# DMGC-IPS-01_2-4.net
KiCad netlist of a schematic drawn in EAGLE
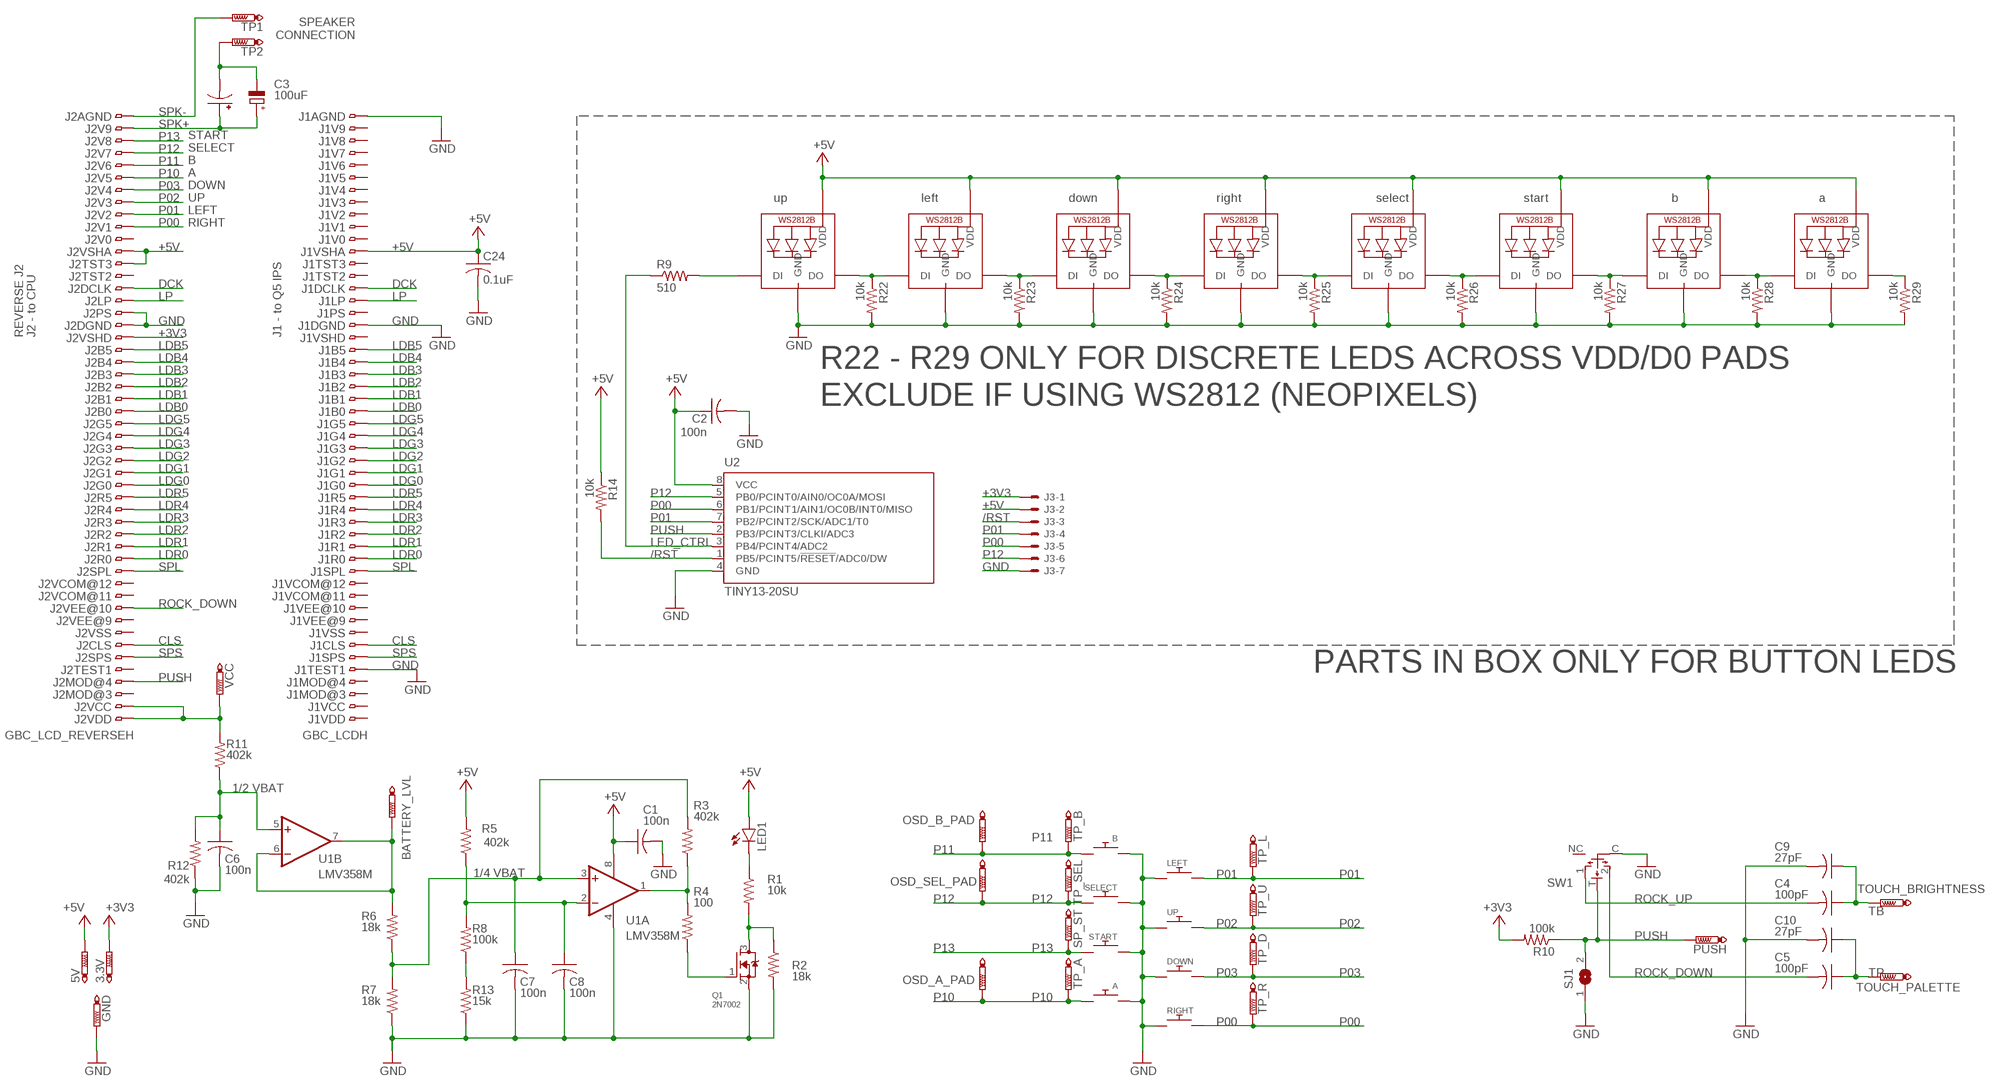
[diagram p0: schematic, sheet 1]

(export (version "E")
  (design (tool "Eeschema 10.0.6"))
  (components
    (comp (ref "3.3V")
      (value "PTR1TP20R")
      (footprint "eagle-import:TP20R")
      (libsource (lib "eagle-import") (part "PTR1TP20R"))
    )
    (comp (ref "5V")
      (value "PTR1TP20R")
      (footprint "eagle-import:TP20R")
      (libsource (lib "eagle-import") (part "PTR1TP20R"))
    )
    (comp (ref "A")
      (value "DMG-BTN")
      (footprint "eagle-import:DMG_BTN1")
      (libsource (lib "eagle-import") (part "DMG_BTN1"))
    )
    (comp (ref "B")
      (value "DMG-BTN")
      (footprint "eagle-import:DMG_BTN1")
      (libsource (lib "eagle-import") (part "DMG_BTN1"))
    )
    (comp (ref "BATTERY_LVL")
      (value "PTR1TP20R")
      (footprint "eagle-import:TP20R")
      (libsource (lib "eagle-import") (part "PTR1TP20R"))
    )
    (comp (ref "C1")
      (value "100n")
      (footprint "eagle-import:C0603")
      (libsource (lib "eagle-import") (part "C-USC0603"))
    )
    (comp (ref "C2")
      (value "100n")
      (footprint "eagle-import:C0603")
      (libsource (lib "eagle-import") (part "C-USC0603"))
    )
    (comp (ref "C3")
      (value "100uF")
      (footprint "eagle-import:CT3528")
      (libsource (lib "eagle-import") (part "CPOL-USCT3528"))
    )
    (comp (ref "C3TH")
      (value "CPOL-EUE2,5-6E")
      (footprint "eagle-import:E2,5-6E")
      (libsource (lib "eagle-import") (part "CPOL-EUE2,5-6E"))
    )
    (comp (ref "C4")
      (value "100pF")
      (footprint "eagle-import:C0603")
      (libsource (lib "eagle-import") (part "C-USC0603"))
    )
    (comp (ref "C5")
      (value "100pF")
      (footprint "eagle-import:C0603")
      (libsource (lib "eagle-import") (part "C-USC0603"))
    )
    (comp (ref "C6")
      (value "100n")
      (footprint "eagle-import:C0603")
      (libsource (lib "eagle-import") (part "C-USC0603"))
    )
    (comp (ref "C7")
      (value "100n")
      (footprint "eagle-import:C0603")
      (libsource (lib "eagle-import") (part "C-USC0603"))
    )
    (comp (ref "C8")
      (value "100n")
      (footprint "eagle-import:C0603")
      (libsource (lib "eagle-import") (part "C-USC0603"))
    )
    (comp (ref "C9")
      (value "27pF")
      (footprint "eagle-import:C0603")
      (libsource (lib "eagle-import") (part "C-USC0603"))
    )
    (comp (ref "C10")
      (value "27pF")
      (footprint "eagle-import:C0603")
      (libsource (lib "eagle-import") (part "C-USC0603"))
    )
    (comp (ref "C24")
      (value "0.1uF")
      (footprint "eagle-import:C0603")
      (libsource (lib "eagle-import") (part "C-USC0603"))
    )
    (comp (ref "DOWN")
      (value "DMG-BTN")
      (footprint "eagle-import:DMG_BTN1")
      (libsource (lib "eagle-import") (part "DMG_BTN1"))
    )
    (comp (ref "GND")
      (value "PTR1TP20R")
      (footprint "eagle-import:TP20R")
      (libsource (lib "eagle-import") (part "PTR1TP20R"))
    )
    (comp (ref "J1")
      (value "GBC_LCDH")
      (footprint "eagle-import:62684-502100AHLF")
      (fields (field (name "MPN") " 62684-502100AHLF"))
      (libsource (lib "eagle-import") (part "GBC_LCDH"))
    )
    (comp (ref "J2")
      (value "GBC_LCD_REVERSEH")
      (footprint "eagle-import:62684-502100AHLF_REVERSE")
      (libsource (lib "eagle-import") (part "GBC_LCD_REVERSEH"))
    )
    (comp (ref "J3")
      (value "C-GRID-07-15-91")
      (footprint "eagle-import:15-91-07")
      (fields (field (name "MF") "MOLEX"))
      (libsource (lib "eagle-import") (part "C-GRID-07-15-91"))
    )
    (comp (ref "LED1")
      (value "LED3MM")
      (footprint "eagle-import:LED3MM")
      (libsource (lib "eagle-import") (part "LED3MM"))
    )
    (comp (ref "LED10")
      (value "WS2812B3535")
      (footprint "eagle-import:LED3535")
      (libsource (lib "eagle-import") (part "WS2812B3535"))
    )
    (comp (ref "LED11")
      (value "WS2812B3535")
      (footprint "eagle-import:LED3535")
      (libsource (lib "eagle-import") (part "WS2812B3535"))
    )
    (comp (ref "LED12")
      (value "WS2812B3535")
      (footprint "eagle-import:LED3535")
      (libsource (lib "eagle-import") (part "WS2812B3535"))
    )
    (comp (ref "LED13")
      (value "WS2812B3535")
      (footprint "eagle-import:LED3535")
      (libsource (lib "eagle-import") (part "WS2812B3535"))
    )
    (comp (ref "LED14")
      (value "WS2812B3535")
      (footprint "eagle-import:LED3535")
      (libsource (lib "eagle-import") (part "WS2812B3535"))
    )
    (comp (ref "LED15")
      (value "WS2812B3535")
      (footprint "eagle-import:LED3535")
      (libsource (lib "eagle-import") (part "WS2812B3535"))
    )
    (comp (ref "LED16")
      (value "WS2812B3535")
      (footprint "eagle-import:LED3535")
      (libsource (lib "eagle-import") (part "WS2812B3535"))
    )
    (comp (ref "LED17")
      (value "WS2812B3535")
      (footprint "eagle-import:LED3535")
      (libsource (lib "eagle-import") (part "WS2812B3535"))
    )
    (comp (ref "LEFT")
      (value "DMG-BTN")
      (footprint "eagle-import:DMG_BTN1")
      (libsource (lib "eagle-import") (part "DMG_BTN1"))
    )
    (comp (ref "OSD_A_PAD")
      (value "PTR1TP20R")
      (footprint "eagle-import:TP20R")
      (libsource (lib "eagle-import") (part "PTR1TP20R"))
    )
    (comp (ref "OSD_B_PAD")
      (value "PTR1TP20R")
      (footprint "eagle-import:TP20R")
      (libsource (lib "eagle-import") (part "PTR1TP20R"))
    )
    (comp (ref "OSD_SEL_PAD")
      (value "PTR1TP20R")
      (footprint "eagle-import:TP20R")
      (libsource (lib "eagle-import") (part "PTR1TP20R"))
    )
    (comp (ref "PUSH")
      (value "PTR1TP20R")
      (footprint "eagle-import:TP20R")
      (libsource (lib "eagle-import") (part "PTR1TP20R"))
    )
    (comp (ref "Q1")
      (value "2N7002")
      (footprint "eagle-import:SOT23")
      (libsource (lib "eagle-import") (part "MOSFET-NREFLOW"))
    )
    (comp (ref "R1")
      (value "10k")
      (footprint "eagle-import:R0603")
      (libsource (lib "eagle-import") (part "R-US_R0603"))
    )
    (comp (ref "R2")
      (value "18k")
      (footprint "eagle-import:R0603")
      (libsource (lib "eagle-import") (part "R-US_R0603"))
    )
    (comp (ref "R3")
      (value "402k")
      (footprint "eagle-import:R0603")
      (libsource (lib "eagle-import") (part "R-US_R0603"))
    )
    (comp (ref "R4")
      (value "100")
      (footprint "eagle-import:R0603")
      (libsource (lib "eagle-import") (part "R-US_R0603"))
    )
    (comp (ref "R5")
      (value "402k")
      (footprint "eagle-import:R0603")
      (libsource (lib "eagle-import") (part "R-US_R0603"))
    )
    (comp (ref "R6")
      (value "18k")
      (footprint "eagle-import:R0603")
      (libsource (lib "eagle-import") (part "R-US_R0603"))
    )
    (comp (ref "R7")
      (value "18k")
      (footprint "eagle-import:R0603")
      (libsource (lib "eagle-import") (part "R-US_R0603"))
    )
    (comp (ref "R8")
      (value "100k")
      (footprint "eagle-import:R0603")
      (libsource (lib "eagle-import") (part "R-US_R0603"))
    )
    (comp (ref "R9")
      (value "510")
      (footprint "eagle-import:R0603")
      (libsource (lib "eagle-import") (part "R-US_R0603"))
    )
    (comp (ref "R10")
      (value "100k")
      (footprint "eagle-import:R0603")
      (libsource (lib "eagle-import") (part "R-US_R0603"))
    )
    (comp (ref "R11")
      (value "402k")
      (footprint "eagle-import:R0603")
      (libsource (lib "eagle-import") (part "R-US_R0603"))
    )
    (comp (ref "R12")
      (value "402k")
      (footprint "eagle-import:R0603")
      (libsource (lib "eagle-import") (part "R-US_R0603"))
    )
    (comp (ref "R13")
      (value "15k")
      (footprint "eagle-import:R0603")
      (libsource (lib "eagle-import") (part "R-US_R0603"))
    )
    (comp (ref "R14")
      (value "10k")
      (footprint "eagle-import:R0603")
      (libsource (lib "eagle-import") (part "R-US_R0603"))
    )
    (comp (ref "R22")
      (value "10k")
      (footprint "eagle-import:R0603")
      (libsource (lib "eagle-import") (part "R-US_R0603"))
    )
    (comp (ref "R23")
      (value "10k")
      (footprint "eagle-import:R0603")
      (libsource (lib "eagle-import") (part "R-US_R0603"))
    )
    (comp (ref "R24")
      (value "10k")
      (footprint "eagle-import:R0603")
      (libsource (lib "eagle-import") (part "R-US_R0603"))
    )
    (comp (ref "R25")
      (value "10k")
      (footprint "eagle-import:R0603")
      (libsource (lib "eagle-import") (part "R-US_R0603"))
    )
    (comp (ref "R26")
      (value "10k")
      (footprint "eagle-import:R0603")
      (libsource (lib "eagle-import") (part "R-US_R0603"))
    )
    (comp (ref "R27")
      (value "10k")
      (footprint "eagle-import:R0603")
      (libsource (lib "eagle-import") (part "R-US_R0603"))
    )
    (comp (ref "R28")
      (value "10k")
      (footprint "eagle-import:R0603")
      (libsource (lib "eagle-import") (part "R-US_R0603"))
    )
    (comp (ref "R29")
      (value "10k")
      (footprint "eagle-import:R0603")
      (libsource (lib "eagle-import") (part "R-US_R0603"))
    )
    (comp (ref "RIGHT")
      (value "DMG-BTN")
      (footprint "eagle-import:DMG_BTN1")
      (libsource (lib "eagle-import") (part "DMG_BTN1"))
    )
    (comp (ref "SELECT")
      (value "DMG-BTN")
      (footprint "eagle-import:DMG_BTN2_TACT2")
      (libsource (lib "eagle-import") (part "DMG_BTN2_TACT2"))
    )
    (comp (ref "SJ1") (value "SJ") (footprint "eagle-import:SJ") (libsource (lib "eagle-import") (part "SJ")))
    (comp (ref "SP_ST")
      (value "PTR1TP20R")
      (footprint "eagle-import:TP20R")
      (libsource (lib "eagle-import") (part "PTR1TP20R"))
    )
    (comp (ref "START")
      (value "DMG-BTN")
      (footprint "eagle-import:DMG_BTN2_TACT2")
      (libsource (lib "eagle-import") (part "DMG_BTN2_TACT2"))
    )
    (comp (ref "SW1")
      (value "NAV_SWITCH")
      (footprint "eagle-import:NAV_SWITCH")
      (libsource (lib "eagle-import") (part "NAV_SWITCH"))
    )
    (comp (ref "TOUCH_BRIGHTNESS")
      (value "PTR1TP20R")
      (footprint "eagle-import:TP20R")
      (libsource (lib "eagle-import") (part "PTR1TP20R"))
    )
    (comp (ref "TOUCH_PALETTE")
      (value "PTR1TP20R")
      (footprint "eagle-import:TP20R")
      (libsource (lib "eagle-import") (part "PTR1TP20R"))
    )
    (comp (ref "TP1")
      (value "PTR1PAD1-13")
      (footprint "eagle-import:P1-13")
      (libsource (lib "eagle-import") (part "testpad_385_PTR1PAD1-13"))
    )
    (comp (ref "TP2")
      (value "PTR1PAD1-13")
      (footprint "eagle-import:P1-13")
      (libsource (lib "eagle-import") (part "testpad_385_PTR1PAD1-13"))
    )
    (comp (ref "TP_A")
      (value "PTR1TP20R")
      (footprint "eagle-import:TP20R")
      (libsource (lib "eagle-import") (part "PTR1TP20R"))
    )
    (comp (ref "TP_B")
      (value "PTR1TP20R")
      (footprint "eagle-import:TP20R")
      (libsource (lib "eagle-import") (part "PTR1TP20R"))
    )
    (comp (ref "TP_D")
      (value "PTR1TP20R")
      (footprint "eagle-import:TP20R")
      (libsource (lib "eagle-import") (part "PTR1TP20R"))
    )
    (comp (ref "TP_L")
      (value "PTR1TP20R")
      (footprint "eagle-import:TP20R")
      (libsource (lib "eagle-import") (part "PTR1TP20R"))
    )
    (comp (ref "TP_R")
      (value "PTR1TP20R")
      (footprint "eagle-import:TP20R")
      (libsource (lib "eagle-import") (part "PTR1TP20R"))
    )
    (comp (ref "TP_SEL")
      (value "PTR1TP20R")
      (footprint "eagle-import:TP20R")
      (libsource (lib "eagle-import") (part "PTR1TP20R"))
    )
    (comp (ref "TP_U")
      (value "PTR1TP20R")
      (footprint "eagle-import:TP20R")
      (libsource (lib "eagle-import") (part "PTR1TP20R"))
    )
    (comp (ref "U1")
      (value "LMV358M")
      (footprint "eagle-import:SO08")
      (libsource (lib "eagle-import") (part "LMV358?M"))
    )
    (comp (ref "U2")
      (value "TINY13-20SU")
      (footprint "eagle-import:8S2")
      (fields (field (name "MPN") "ATTINY13-20SU"))
      (libsource (lib "eagle-import") (part "TINY13SU-20"))
    )
    (comp (ref "UP")
      (value "DMG-BTN")
      (footprint "eagle-import:DMG_BTN1")
      (libsource (lib "eagle-import") (part "DMG_BTN1"))
    )
    (comp (ref "VCC")
      (value "PTR1TP20R")
      (footprint "eagle-import:TP20R")
      (libsource (lib "eagle-import") (part "PTR1TP20R"))
    )
  )
  (nets
    (net (code "1") (name "+3V3") (class "Default")
      (node (ref "3.3V") (pin "TP") (pinfunction "TP_TP") (pintype "input"))
      (node (ref "J2") (pin "19") (pinfunction "1_19") (pintype "passive"))
      (node (ref "J3") (pin "1") (pinfunction "S_1") (pintype "passive"))
      (node (ref "R10") (pin "2") (pinfunction "2_2") (pintype "passive"))
    )
    (net (code "2") (name "+5V") (class "Default")
      (node (ref "5V") (pin "TP") (pinfunction "TP_TP") (pintype "input"))
      (node (ref "C1") (pin "1") (pinfunction "1_1") (pintype "passive"))
      (node (ref "C2") (pin "1") (pinfunction "1_1") (pintype "passive"))
      (node (ref "C24") (pin "1") (pinfunction "1_1") (pintype "passive"))
      (node (ref "J1") (pin "39") (pinfunction "1_39") (pintype "passive"))
      (node (ref "J2") (pin "12") (pinfunction "1_12") (pintype "passive"))
      (node (ref "J2") (pin "13") (pinfunction "1_13") (pintype "passive"))
      (node (ref "J3") (pin "2") (pinfunction "S_2") (pintype "passive"))
      (node (ref "LED1") (pin "A") (pinfunction "A_A") (pintype "passive"))
      (node (ref "LED10") (pin "4") (pinfunction "VDD_4") (pintype "power_in"))
      (node (ref "LED11") (pin "4") (pinfunction "VDD_4") (pintype "power_in"))
      (node (ref "LED12") (pin "4") (pinfunction "VDD_4") (pintype "power_in"))
      (node (ref "LED13") (pin "4") (pinfunction "VDD_4") (pintype "power_in"))
      (node (ref "LED14") (pin "4") (pinfunction "VDD_4") (pintype "power_in"))
      (node (ref "LED15") (pin "4") (pinfunction "VDD_4") (pintype "power_in"))
      (node (ref "LED16") (pin "4") (pinfunction "VDD_4") (pintype "power_in"))
      (node (ref "LED17") (pin "4") (pinfunction "VDD_4") (pintype "power_in"))
      (node (ref "R14") (pin "1") (pinfunction "1_1") (pintype "passive"))
      (node (ref "R5") (pin "2") (pinfunction "2_2") (pintype "passive"))
      (node (ref "U1") (pin "8") (pinfunction "V+_8") (pintype "power_in"))
      (node (ref "U2") (pin "8") (pinfunction "VCC_8") (pintype "power_in"))
    )
    (net (code "3") (name "/CLS") (class "Default")
      (node (ref "J1") (pin "7") (pinfunction "1_7") (pintype "passive"))
      (node (ref "J2") (pin "44") (pinfunction "1_44") (pintype "passive"))
    )
    (net (code "4") (name "/DCK") (class "Default")
      (node (ref "J1") (pin "36") (pinfunction "1_36") (pintype "passive"))
      (node (ref "J2") (pin "15") (pinfunction "1_15") (pintype "passive"))
    )
    (net (code "5") (name "/LDB0") (class "Default")
      (node (ref "J1") (pin "26") (pinfunction "1_26") (pintype "passive"))
      (node (ref "J2") (pin "25") (pinfunction "1_25") (pintype "passive"))
    )
    (net (code "6") (name "/LDB1") (class "Default")
      (node (ref "J1") (pin "27") (pinfunction "1_27") (pintype "passive"))
      (node (ref "J2") (pin "24") (pinfunction "1_24") (pintype "passive"))
    )
    (net (code "7") (name "/LDB2") (class "Default")
      (node (ref "J1") (pin "28") (pinfunction "1_28") (pintype "passive"))
      (node (ref "J2") (pin "23") (pinfunction "1_23") (pintype "passive"))
    )
    (net (code "8") (name "/LDB3") (class "Default")
      (node (ref "J1") (pin "29") (pinfunction "1_29") (pintype "passive"))
      (node (ref "J2") (pin "22") (pinfunction "1_22") (pintype "passive"))
    )
    (net (code "9") (name "/LDB4") (class "Default")
      (node (ref "J1") (pin "30") (pinfunction "1_30") (pintype "passive"))
      (node (ref "J2") (pin "21") (pinfunction "1_21") (pintype "passive"))
    )
    (net (code "10") (name "/LDB5") (class "Default")
      (node (ref "J1") (pin "31") (pinfunction "1_31") (pintype "passive"))
      (node (ref "J2") (pin "20") (pinfunction "1_20") (pintype "passive"))
    )
    (net (code "11") (name "/LDG0") (class "Default")
      (node (ref "J1") (pin "20") (pinfunction "1_20") (pintype "passive"))
      (node (ref "J2") (pin "31") (pinfunction "1_31") (pintype "passive"))
    )
    (net (code "12") (name "/LDG1") (class "Default")
      (node (ref "J1") (pin "21") (pinfunction "1_21") (pintype "passive"))
      (node (ref "J2") (pin "30") (pinfunction "1_30") (pintype "passive"))
    )
    (net (code "13") (name "/LDG2") (class "Default")
      (node (ref "J1") (pin "22") (pinfunction "1_22") (pintype "passive"))
      (node (ref "J2") (pin "29") (pinfunction "1_29") (pintype "passive"))
    )
    (net (code "14") (name "/LDG3") (class "Default")
      (node (ref "J1") (pin "23") (pinfunction "1_23") (pintype "passive"))
      (node (ref "J2") (pin "28") (pinfunction "1_28") (pintype "passive"))
    )
    (net (code "15") (name "/LDG4") (class "Default")
      (node (ref "J1") (pin "24") (pinfunction "1_24") (pintype "passive"))
      (node (ref "J2") (pin "27") (pinfunction "1_27") (pintype "passive"))
    )
    (net (code "16") (name "/LDG5") (class "Default")
      (node (ref "J1") (pin "25") (pinfunction "1_25") (pintype "passive"))
      (node (ref "J2") (pin "26") (pinfunction "1_26") (pintype "passive"))
    )
    (net (code "17") (name "/LDR0") (class "Default")
      (node (ref "J1") (pin "14") (pinfunction "1_14") (pintype "passive"))
      (node (ref "J2") (pin "37") (pinfunction "1_37") (pintype "passive"))
    )
    (net (code "18") (name "/LDR1") (class "Default")
      (node (ref "J1") (pin "15") (pinfunction "1_15") (pintype "passive"))
      (node (ref "J2") (pin "36") (pinfunction "1_36") (pintype "passive"))
    )
    (net (code "19") (name "/LDR2") (class "Default")
      (node (ref "J1") (pin "16") (pinfunction "1_16") (pintype "passive"))
      (node (ref "J2") (pin "35") (pinfunction "1_35") (pintype "passive"))
    )
    (net (code "20") (name "/LDR3") (class "Default")
      (node (ref "J1") (pin "17") (pinfunction "1_17") (pintype "passive"))
      (node (ref "J2") (pin "34") (pinfunction "1_34") (pintype "passive"))
    )
    (net (code "21") (name "/LDR4") (class "Default")
      (node (ref "J1") (pin "18") (pinfunction "1_18") (pintype "passive"))
      (node (ref "J2") (pin "33") (pinfunction "1_33") (pintype "passive"))
    )
    (net (code "22") (name "/LDR5") (class "Default")
      (node (ref "J1") (pin "19") (pinfunction "1_19") (pintype "passive"))
      (node (ref "J2") (pin "32") (pinfunction "1_32") (pintype "passive"))
    )
    (net (code "23") (name "/LED_CTRL") (class "Default")
      (node (ref "R9") (pin "1") (pinfunction "1_1") (pintype "passive"))
      (node (ref "U2") (pin "3") (pinfunction "PB4/PCINT4/ADC2_3") (pintype "bidirectional"))
    )
    (net (code "24") (name "/LP") (class "Default")
      (node (ref "J1") (pin "35") (pinfunction "1_35") (pintype "passive"))
      (node (ref "J2") (pin "16") (pinfunction "1_16") (pintype "passive"))
    )
    (net (code "25") (name "/P00") (class "Default")
      (node (ref "J2") (pin "10") (pinfunction "1_10") (pintype "passive"))
      (node (ref "J3") (pin "5") (pinfunction "S_5") (pintype "passive"))
      (node (ref "RIGHT") (pin "P$1") (pinfunction "P$2_P$1") (pintype "passive"))
      (node (ref "TP_R") (pin "TP") (pinfunction "TP_TP") (pintype "input"))
      (node (ref "U2") (pin "6") (pinfunction "PB1/PCINT1/AIN1/OC0B/INT0/MISO_6") (pintype "bidirectional"))
    )
    (net (code "26") (name "/P01") (class "Default")
      (node (ref "J2") (pin "9") (pinfunction "1_9") (pintype "passive"))
      (node (ref "J3") (pin "4") (pinfunction "S_4") (pintype "passive"))
      (node (ref "LEFT") (pin "P$1") (pinfunction "P$2_P$1") (pintype "passive"))
      (node (ref "TP_L") (pin "TP") (pinfunction "TP_TP") (pintype "input"))
      (node (ref "U2") (pin "7") (pinfunction "PB2/PCINT2/SCK/ADC1/T0_7") (pintype "bidirectional"))
    )
    (net (code "27") (name "/P02") (class "Default")
      (node (ref "J2") (pin "8") (pinfunction "1_8") (pintype "passive"))
      (node (ref "TP_U") (pin "TP") (pinfunction "TP_TP") (pintype "input"))
      (node (ref "UP") (pin "P$1") (pinfunction "P$2_P$1") (pintype "passive"))
    )
    (net (code "28") (name "/P03") (class "Default")
      (node (ref "DOWN") (pin "P$1") (pinfunction "P$2_P$1") (pintype "passive"))
      (node (ref "J2") (pin "7") (pinfunction "1_7") (pintype "passive"))
      (node (ref "TP_D") (pin "TP") (pinfunction "TP_TP") (pintype "input"))
    )
    (net (code "29") (name "/P10") (class "Default")
      (node (ref "A") (pin "P$1") (pinfunction "P$2_P$1") (pintype "passive"))
      (node (ref "J2") (pin "6") (pinfunction "1_6") (pintype "passive"))
      (node (ref "OSD_A_PAD") (pin "TP") (pinfunction "TP_TP") (pintype "input"))
      (node (ref "TP_A") (pin "TP") (pinfunction "TP_TP") (pintype "input"))
    )
    (net (code "30") (name "/P11") (class "Default")
      (node (ref "B") (pin "P$1") (pinfunction "P$2_P$1") (pintype "passive"))
      (node (ref "J2") (pin "5") (pinfunction "1_5") (pintype "passive"))
      (node (ref "OSD_B_PAD") (pin "TP") (pinfunction "TP_TP") (pintype "input"))
      (node (ref "TP_B") (pin "TP") (pinfunction "TP_TP") (pintype "input"))
    )
    (net (code "31") (name "/P12") (class "Default")
      (node (ref "J2") (pin "4") (pinfunction "1_4") (pintype "passive"))
      (node (ref "J3") (pin "6") (pinfunction "S_6") (pintype "passive"))
      (node (ref "OSD_SEL_PAD") (pin "TP") (pinfunction "TP_TP") (pintype "input"))
      (node (ref "SELECT") (pin "P$2") (pinfunction "P$2_P$2") (pintype "passive"))
      (node (ref "TP_SEL") (pin "TP") (pinfunction "TP_TP") (pintype "input"))
      (node (ref "U2") (pin "5") (pinfunction "PB0/PCINT0/AIN0/OC0A/MOSI_5") (pintype "bidirectional"))
    )
    (net (code "32") (name "/P13") (class "Default")
      (node (ref "J2") (pin "3") (pinfunction "1_3") (pintype "passive"))
      (node (ref "SP_ST") (pin "TP") (pinfunction "TP_TP") (pintype "input"))
      (node (ref "START") (pin "P$2") (pinfunction "P$2_P$2") (pintype "passive"))
    )
    (net (code "33") (name "/PUSH") (class "Default")
      (node (ref "J2") (pin "47") (pinfunction "1_47") (pintype "passive"))
      (node (ref "PUSH") (pin "TP") (pinfunction "TP_TP") (pintype "input"))
      (node (ref "R10") (pin "1") (pinfunction "1_1") (pintype "passive"))
      (node (ref "SJ1") (pin "2") (pinfunction "2_2") (pintype "passive"))
      (node (ref "SW1") (pin "T") (pinfunction "T_T") (pintype "passive"))
      (node (ref "U2") (pin "2") (pinfunction "PB3/PCINT3/CLKI/ADC3_2") (pintype "bidirectional"))
    )
    (net (code "34") (name "/ROCK_DOWN") (class "Default")
      (node (ref "C5") (pin "2") (pinfunction "2_2") (pintype "passive"))
      (node (ref "J2") (pin "41") (pinfunction "1_41") (pintype "passive"))
      (node (ref "SW1") (pin "2") (pinfunction "2_2") (pintype "passive"))
    )
    (net (code "35") (name "/ROCK_UP") (class "Default")
      (node (ref "C4") (pin "2") (pinfunction "2_2") (pintype "passive"))
      (node (ref "SW1") (pin "1") (pinfunction "1_1") (pintype "passive"))
    )
    (net (code "36") (name "/SPK+") (class "Default")
      (node (ref "C3") (pin "+") (pinfunction "+_+") (pintype "passive"))
      (node (ref "C3TH") (pin "+") (pinfunction "+_+") (pintype "passive"))
      (node (ref "J2") (pin "2") (pinfunction "1_2") (pintype "passive"))
    )
    (net (code "37") (name "/SPK-") (class "Default")
      (node (ref "J2") (pin "1") (pinfunction "1_1") (pintype "passive"))
      (node (ref "TP1") (pin "TP") (pinfunction "TP_TP") (pintype "input"))
    )
    (net (code "38") (name "/SPL") (class "Default")
      (node (ref "J1") (pin "13") (pinfunction "1_13") (pintype "passive"))
      (node (ref "J2") (pin "38") (pinfunction "1_38") (pintype "passive"))
    )
    (net (code "39") (name "/SPS") (class "Default")
      (node (ref "J1") (pin "6") (pinfunction "1_6") (pintype "passive"))
      (node (ref "J2") (pin "45") (pinfunction "1_45") (pintype "passive"))
    )
    (net (code "40") (name "/TB") (class "Default")
      (node (ref "C4") (pin "1") (pinfunction "1_1") (pintype "passive"))
      (node (ref "C9") (pin "1") (pinfunction "1_1") (pintype "passive"))
      (node (ref "TOUCH_BRIGHTNESS") (pin "TP") (pinfunction "TP_TP") (pintype "input"))
    )
    (net (code "41") (name "/TP") (class "Default")
      (node (ref "C10") (pin "1") (pinfunction "1_1") (pintype "passive"))
      (node (ref "C5") (pin "1") (pinfunction "1_1") (pintype "passive"))
      (node (ref "TOUCH_PALETTE") (pin "TP") (pinfunction "TP_TP") (pintype "input"))
    )
    (net (code "42") (name "/{slash}RST") (class "Default")
      (node (ref "J3") (pin "3") (pinfunction "S_3") (pintype "passive"))
      (node (ref "R14") (pin "2") (pinfunction "2_2") (pintype "passive"))
      (node (ref "U2") (pin "1") (pinfunction "PB5/PCINT5/~{RESET}/ADC0/DW_1") (pintype "bidirectional"))
    )
    (net (code "43") (name "GND") (class "Default")
      (node (ref "A") (pin "P$2") (pinfunction "P$1_P$2") (pintype "passive"))
      (node (ref "B") (pin "P$2") (pinfunction "P$1_P$2") (pintype "passive"))
      (node (ref "C1") (pin "2") (pinfunction "2_2") (pintype "passive"))
      (node (ref "C10") (pin "2") (pinfunction "2_2") (pintype "passive"))
      (node (ref "C2") (pin "2") (pinfunction "2_2") (pintype "passive"))
      (node (ref "C24") (pin "2") (pinfunction "2_2") (pintype "passive"))
      (node (ref "C6") (pin "2") (pinfunction "2_2") (pintype "passive"))
      (node (ref "C7") (pin "2") (pinfunction "2_2") (pintype "passive"))
      (node (ref "C8") (pin "2") (pinfunction "2_2") (pintype "passive"))
      (node (ref "C9") (pin "2") (pinfunction "2_2") (pintype "passive"))
      (node (ref "DOWN") (pin "P$2") (pinfunction "P$1_P$2") (pintype "passive"))
      (node (ref "GND") (pin "TP") (pinfunction "TP_TP") (pintype "input"))
      (node (ref "J1") (pin "33") (pinfunction "1_33") (pintype "passive"))
      (node (ref "J1") (pin "5") (pinfunction "1_5") (pintype "passive"))
      (node (ref "J1") (pin "50") (pinfunction "1_50") (pintype "passive"))
      (node (ref "J2") (pin "17") (pinfunction "1_17") (pintype "passive"))
      (node (ref "J2") (pin "18") (pinfunction "1_18") (pintype "passive"))
      (node (ref "J3") (pin "7") (pinfunction "S_7") (pintype "passive"))
      (node (ref "LED10") (pin "2") (pinfunction "GND_2") (pintype "power_in"))
      (node (ref "LED11") (pin "2") (pinfunction "GND_2") (pintype "power_in"))
      (node (ref "LED12") (pin "2") (pinfunction "GND_2") (pintype "power_in"))
      (node (ref "LED13") (pin "2") (pinfunction "GND_2") (pintype "power_in"))
      (node (ref "LED14") (pin "2") (pinfunction "GND_2") (pintype "power_in"))
      (node (ref "LED15") (pin "2") (pinfunction "GND_2") (pintype "power_in"))
      (node (ref "LED16") (pin "2") (pinfunction "GND_2") (pintype "power_in"))
      (node (ref "LED17") (pin "2") (pinfunction "GND_2") (pintype "power_in"))
      (node (ref "LEFT") (pin "P$2") (pinfunction "P$1_P$2") (pintype "passive"))
      (node (ref "Q1") (pin "2") (pinfunction "S_2") (pintype "bidirectional"))
      (node (ref "R12") (pin "1") (pinfunction "1_1") (pintype "passive"))
      (node (ref "R13") (pin "1") (pinfunction "1_1") (pintype "passive"))
      (node (ref "R2") (pin "2") (pinfunction "2_2") (pintype "passive"))
      (node (ref "R22") (pin "2") (pinfunction "2_2") (pintype "passive"))
      (node (ref "R23") (pin "2") (pinfunction "2_2") (pintype "passive"))
      (node (ref "R24") (pin "2") (pinfunction "2_2") (pintype "passive"))
      (node (ref "R25") (pin "2") (pinfunction "2_2") (pintype "passive"))
      (node (ref "R26") (pin "2") (pinfunction "2_2") (pintype "passive"))
      (node (ref "R27") (pin "2") (pinfunction "2_2") (pintype "passive"))
      (node (ref "R28") (pin "2") (pinfunction "2_2") (pintype "passive"))
      (node (ref "R29") (pin "2") (pinfunction "2_2") (pintype "passive"))
      (node (ref "R7") (pin "1") (pinfunction "1_1") (pintype "passive"))
      (node (ref "RIGHT") (pin "P$2") (pinfunction "P$1_P$2") (pintype "passive"))
      (node (ref "SELECT") (pin "P$1") (pinfunction "P$1_P$1") (pintype "passive"))
      (node (ref "SJ1") (pin "1") (pinfunction "1_1") (pintype "passive"))
      (node (ref "START") (pin "P$1") (pinfunction "P$1_P$1") (pintype "passive"))
      (node (ref "SW1") (pin "C") (pinfunction "C_C") (pintype "passive"))
      (node (ref "U1") (pin "4") (pinfunction "V-_4") (pintype "power_in"))
      (node (ref "U2") (pin "4") (pinfunction "GND_4") (pintype "power_in"))
      (node (ref "UP") (pin "P$2") (pinfunction "P$1_P$2") (pintype "passive"))
    )
    (net (code "44") (name "Net-(C3-Pad-)") (class "Default")
      (node (ref "C3") (pin "-") (pinfunction "-_-") (pintype "passive"))
      (node (ref "C3TH") (pin "-") (pinfunction "-_-") (pintype "passive"))
      (node (ref "TP2") (pin "TP") (pinfunction "TP_TP") (pintype "input"))
    )
    (net (code "45") (name "Net-(J2AP-1)") (class "Default")
      (node (ref "J2") (pin "49") (pinfunction "1_49") (pintype "passive"))
      (node (ref "J2") (pin "50") (pinfunction "1_50") (pintype "passive"))
      (node (ref "R11") (pin "2") (pinfunction "2_2") (pintype "passive"))
      (node (ref "VCC") (pin "TP") (pinfunction "TP_TP") (pintype "input"))
    )
    (net (code "46") (name "Net-(LED1-C)") (class "Default")
      (node (ref "LED1") (pin "K") (pinfunction "C_K") (pintype "passive"))
      (node (ref "R1") (pin "1") (pinfunction "1_1") (pintype "passive"))
    )
    (net (code "47") (name "Net-(LED10-DI)") (class "Default")
      (node (ref "LED10") (pin "3") (pinfunction "DI_3") (pintype "input"))
      (node (ref "R9") (pin "2") (pinfunction "2_2") (pintype "passive"))
    )
    (net (code "48") (name "Net-(LED10-DO)") (class "Default")
      (node (ref "LED10") (pin "1") (pinfunction "DO_1") (pintype "output"))
      (node (ref "LED14") (pin "3") (pinfunction "DI_3") (pintype "input"))
      (node (ref "R22") (pin "1") (pinfunction "1_1") (pintype "passive"))
    )
    (net (code "49") (name "Net-(LED11-DI)") (class "Default")
      (node (ref "LED11") (pin "3") (pinfunction "DI_3") (pintype "input"))
      (node (ref "LED14") (pin "1") (pinfunction "DO_1") (pintype "output"))
      (node (ref "R23") (pin "1") (pinfunction "1_1") (pintype "passive"))
    )
    (net (code "50") (name "Net-(LED11-DO)") (class "Default")
      (node (ref "LED11") (pin "1") (pinfunction "DO_1") (pintype "output"))
      (node (ref "LED12") (pin "3") (pinfunction "DI_3") (pintype "input"))
      (node (ref "R24") (pin "1") (pinfunction "1_1") (pintype "passive"))
    )
    (net (code "51") (name "Net-(LED12-DO)") (class "Default")
      (node (ref "LED12") (pin "1") (pinfunction "DO_1") (pintype "output"))
      (node (ref "LED17") (pin "3") (pinfunction "DI_3") (pintype "input"))
      (node (ref "R25") (pin "1") (pinfunction "1_1") (pintype "passive"))
    )
    (net (code "52") (name "Net-(LED13-DI)") (class "Default")
      (node (ref "LED13") (pin "3") (pinfunction "DI_3") (pintype "input"))
      (node (ref "LED17") (pin "1") (pinfunction "DO_1") (pintype "output"))
      (node (ref "R26") (pin "1") (pinfunction "1_1") (pintype "passive"))
    )
    (net (code "53") (name "Net-(LED13-DO)") (class "Default")
      (node (ref "LED13") (pin "1") (pinfunction "DO_1") (pintype "output"))
      (node (ref "LED16") (pin "3") (pinfunction "DI_3") (pintype "input"))
      (node (ref "R27") (pin "1") (pinfunction "1_1") (pintype "passive"))
    )
    (net (code "54") (name "Net-(LED15-DI)") (class "Default")
      (node (ref "LED15") (pin "3") (pinfunction "DI_3") (pintype "input"))
      (node (ref "LED16") (pin "1") (pinfunction "DO_1") (pintype "output"))
      (node (ref "R28") (pin "1") (pinfunction "1_1") (pintype "passive"))
    )
    (net (code "55") (name "Net-(LED15-DO)") (class "Default")
      (node (ref "LED15") (pin "1") (pinfunction "DO_1") (pintype "output"))
      (node (ref "R29") (pin "1") (pinfunction "1_1") (pintype "passive"))
    )
    (net (code "56") (name "Net-(Q1-D)") (class "Default")
      (node (ref "Q1") (pin "3") (pinfunction "D_3") (pintype "bidirectional"))
      (node (ref "R1") (pin "2") (pinfunction "2_2") (pintype "passive"))
      (node (ref "R2") (pin "1") (pinfunction "1_1") (pintype "passive"))
    )
    (net (code "57") (name "Net-(Q1-G)") (class "Default")
      (node (ref "Q1") (pin "1") (pinfunction "G_1") (pintype "bidirectional"))
      (node (ref "R4") (pin "1") (pinfunction "1_1") (pintype "passive"))
    )
    (net (code "58") (name "Net-(R13-Pad2)") (class "Default")
      (node (ref "R13") (pin "2") (pinfunction "2_2") (pintype "passive"))
      (node (ref "R8") (pin "1") (pinfunction "1_1") (pintype "passive"))
    )
    (net (code "59") (name "Net-(U1A-+IN)") (class "Default")
      (node (ref "C7") (pin "1") (pinfunction "1_1") (pintype "passive"))
      (node (ref "R3") (pin "2") (pinfunction "2_2") (pintype "passive"))
      (node (ref "R6") (pin "1") (pinfunction "1_1") (pintype "passive"))
      (node (ref "R7") (pin "2") (pinfunction "2_2") (pintype "passive"))
      (node (ref "U1") (pin "3") (pinfunction "+IN_3") (pintype "input"))
    )
    (net (code "60") (name "Net-(U1A--IN)") (class "Default")
      (node (ref "C8") (pin "1") (pinfunction "1_1") (pintype "passive"))
      (node (ref "R5") (pin "1") (pinfunction "1_1") (pintype "passive"))
      (node (ref "R8") (pin "2") (pinfunction "2_2") (pintype "passive"))
      (node (ref "U1") (pin "2") (pinfunction "-IN_2") (pintype "input"))
    )
    (net (code "61") (name "Net-(U1A-OUT)") (class "Default")
      (node (ref "R3") (pin "1") (pinfunction "1_1") (pintype "passive"))
      (node (ref "R4") (pin "2") (pinfunction "2_2") (pintype "passive"))
      (node (ref "U1") (pin "1") (pinfunction "OUT_1") (pintype "output"))
    )
    (net (code "62") (name "Net-(U1B-+IN)") (class "Default")
      (node (ref "C6") (pin "1") (pinfunction "1_1") (pintype "passive"))
      (node (ref "R11") (pin "1") (pinfunction "1_1") (pintype "passive"))
      (node (ref "R12") (pin "2") (pinfunction "2_2") (pintype "passive"))
      (node (ref "U1") (pin "5") (pinfunction "+IN_5") (pintype "input"))
    )
    (net (code "63") (name "Net-(U1B--IN)") (class "Default")
      (node (ref "BATTERY_LVL") (pin "TP") (pinfunction "TP_TP") (pintype "input"))
      (node (ref "R6") (pin "2") (pinfunction "2_2") (pintype "passive"))
      (node (ref "U1") (pin "6") (pinfunction "-IN_6") (pintype "input"))
      (node (ref "U1") (pin "7") (pinfunction "OUT_7") (pintype "output"))
    )
    (net (code "64") (name "unconnected-(J1-Pad1)") (class "Default")
      (node (ref "J1") (pin "1") (pinfunction "1_1") (pintype "passive"))
    )
    (net (code "65") (name "unconnected-(J1AD-1-Pad37)") (class "Default")
      (node (ref "J1") (pin "37") (pinfunction "1_37") (pintype "passive"))
    )
    (net (code "66") (name "unconnected-(J1AE-1-Pad38)") (class "Default")
      (node (ref "J1") (pin "38") (pinfunction "1_38") (pintype "passive"))
    )
    (net (code "67") (name "unconnected-(J1AF-1-Pad40)") (class "Default")
      (node (ref "J1") (pin "40") (pinfunction "1_40") (pintype "passive"))
    )
    (net (code "68") (name "unconnected-(J1AG-1-Pad41)") (class "Default")
      (node (ref "J1") (pin "41") (pinfunction "1_41") (pintype "passive"))
    )
    (net (code "69") (name "unconnected-(J1AH-1-Pad42)") (class "Default")
      (node (ref "J1") (pin "42") (pinfunction "1_42") (pintype "passive"))
    )
    (net (code "70") (name "unconnected-(J1AI-1-Pad43)") (class "Default")
      (node (ref "J1") (pin "43") (pinfunction "1_43") (pintype "passive"))
    )
    (net (code "71") (name "unconnected-(J1AJ-1-Pad44)") (class "Default")
      (node (ref "J1") (pin "44") (pinfunction "1_44") (pintype "passive"))
    )
    (net (code "72") (name "unconnected-(J1AK-1-Pad45)") (class "Default")
      (node (ref "J1") (pin "45") (pinfunction "1_45") (pintype "passive"))
    )
    (net (code "73") (name "unconnected-(J1AL-1-Pad46)") (class "Default")
      (node (ref "J1") (pin "46") (pinfunction "1_46") (pintype "passive"))
    )
    (net (code "74") (name "unconnected-(J1AM-1-Pad47)") (class "Default")
      (node (ref "J1") (pin "47") (pinfunction "1_47") (pintype "passive"))
    )
    (net (code "75") (name "unconnected-(J1AN-1-Pad48)") (class "Default")
      (node (ref "J1") (pin "48") (pinfunction "1_48") (pintype "passive"))
    )
    (net (code "76") (name "unconnected-(J1AO-1-Pad49)") (class "Default")
      (node (ref "J1") (pin "49") (pinfunction "1_49") (pintype "passive"))
    )
    (net (code "77") (name "unconnected-(J1AP-1-Pad2)") (class "Default")
      (node (ref "J1") (pin "2") (pinfunction "1_2") (pintype "passive"))
    )
    (net (code "78") (name "unconnected-(J1AQ-1-Pad11)") (class "Default")
      (node (ref "J1") (pin "11") (pinfunction "1_11") (pintype "passive"))
    )
    (net (code "79") (name "unconnected-(J1AR-1-Pad12)") (class "Default")
      (node (ref "J1") (pin "12") (pinfunction "1_12") (pintype "passive"))
    )
    (net (code "80") (name "unconnected-(J1AT-1-Pad10)") (class "Default")
      (node (ref "J1") (pin "10") (pinfunction "1_10") (pintype "passive"))
    )
    (net (code "81") (name "unconnected-(J1AU-1-Pad9)") (class "Default")
      (node (ref "J1") (pin "9") (pinfunction "1_9") (pintype "passive"))
    )
    (net (code "82") (name "unconnected-(J1AW-1-Pad32)") (class "Default")
      (node (ref "J1") (pin "32") (pinfunction "1_32") (pintype "passive"))
    )
    (net (code "83") (name "unconnected-(J1AX-1-Pad8)") (class "Default")
      (node (ref "J1") (pin "8") (pinfunction "1_8") (pintype "passive"))
    )
    (net (code "84") (name "unconnected-(J1R-1-Pad3)") (class "Default")
      (node (ref "J1") (pin "3") (pinfunction "1_3") (pintype "passive"))
    )
    (net (code "85") (name "unconnected-(J1S-1-Pad4)") (class "Default")
      (node (ref "J1") (pin "4") (pinfunction "1_4") (pintype "passive"))
    )
    (net (code "86") (name "unconnected-(J1T-1-Pad34)") (class "Default")
      (node (ref "J1") (pin "34") (pinfunction "1_34") (pintype "passive"))
    )
    (net (code "87") (name "unconnected-(J2AC-1-Pad46)") (class "Default")
      (node (ref "J2") (pin "46") (pinfunction "1_46") (pintype "passive"))
    )
    (net (code "88") (name "unconnected-(J2AD-1-Pad14)") (class "Default")
      (node (ref "J2") (pin "14") (pinfunction "1_14") (pintype "passive"))
    )
    (net (code "89") (name "unconnected-(J2AF-1-Pad11)") (class "Default")
      (node (ref "J2") (pin "11") (pinfunction "1_11") (pintype "passive"))
    )
    (net (code "90") (name "unconnected-(J2AQ-1-Pad40)") (class "Default")
      (node (ref "J2") (pin "40") (pinfunction "1_40") (pintype "passive"))
    )
    (net (code "91") (name "unconnected-(J2AR-1-Pad39)") (class "Default")
      (node (ref "J2") (pin "39") (pinfunction "1_39") (pintype "passive"))
    )
    (net (code "92") (name "unconnected-(J2AU-1-Pad42)") (class "Default")
      (node (ref "J2") (pin "42") (pinfunction "1_42") (pintype "passive"))
    )
    (net (code "93") (name "unconnected-(J2AX-1-Pad43)") (class "Default")
      (node (ref "J2") (pin "43") (pinfunction "1_43") (pintype "passive"))
    )
    (net (code "94") (name "unconnected-(J2R-1-Pad48)") (class "Default")
      (node (ref "J2") (pin "48") (pinfunction "1_48") (pintype "passive"))
    )
    (net (code "95") (name "unconnected-(SW1-PadNC)") (class "Default")
      (node (ref "SW1") (pin "NC") (pinfunction "NC_NC") (pintype "no_connect"))
    )
  )
)
